# Sheet1.net
KiCad netlist of a schematic drawn in Altium Designer
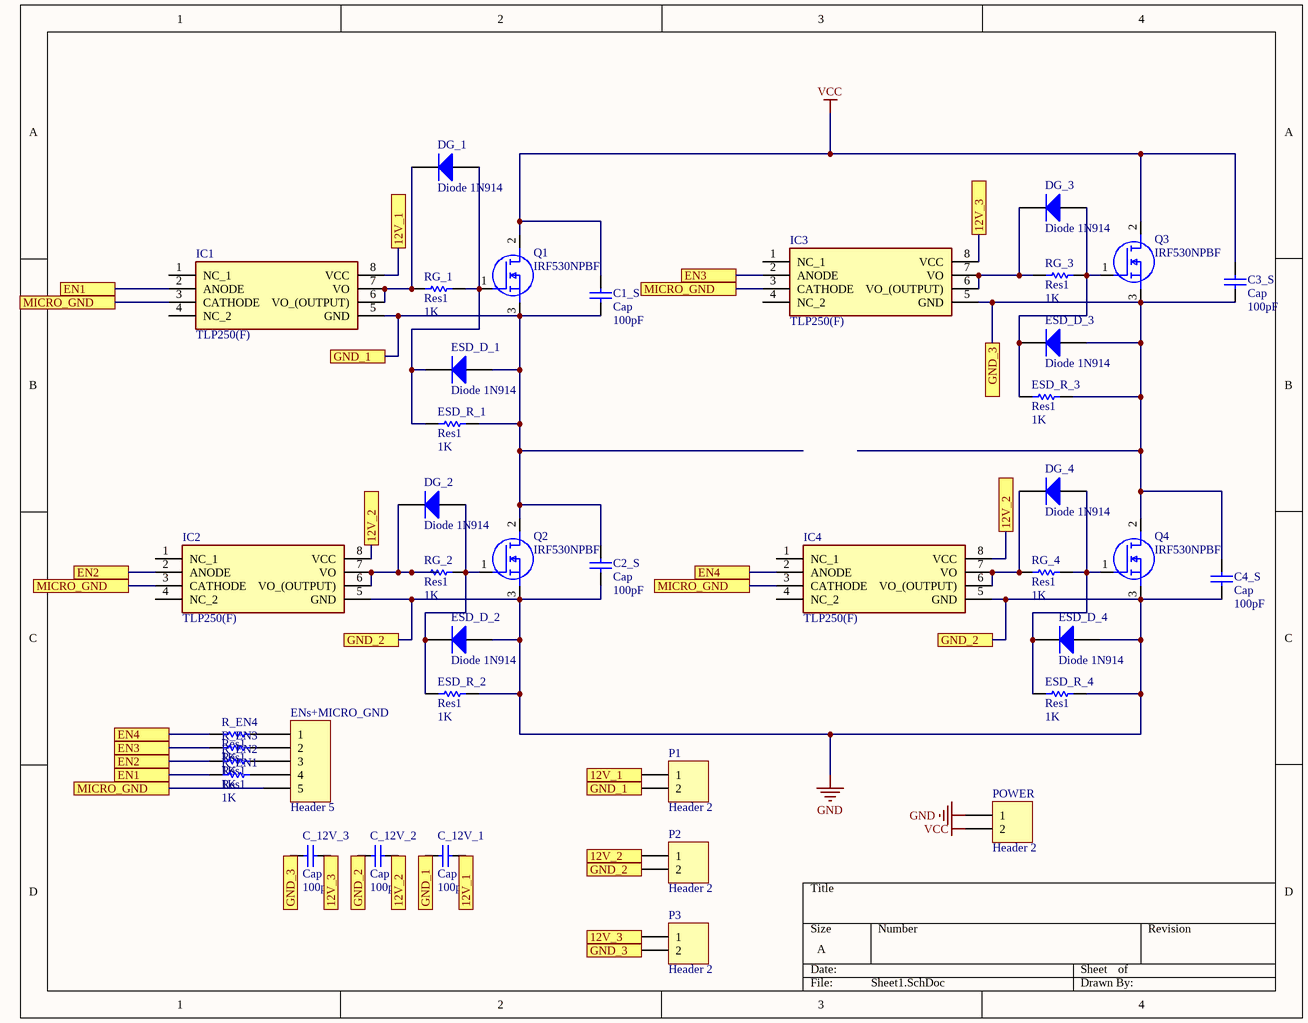
[diagram p0: Sheet1.SchDoc]

(export (version "E")
  (design (tool "Eeschema 10.0.6"))
  (components
    (comp (ref "C1_S")
      (value "Cap")
      (footprint "RAD-0.3")
      (description "Capacitor")
      (fields (field (name "ALTIUM_VALUE") "100pF") (field (name "PUBLISHER") "Altium Limited"))
      (libsource (lib "Miscellaneous Devices") (part "Cap"))
    )
    (comp (ref "C2_S")
      (value "Cap")
      (footprint "RAD-0.3")
      (description "Capacitor")
      (fields (field (name "ALTIUM_VALUE") "100pF") (field (name "PUBLISHER") "Altium Limited"))
      (libsource (lib "Miscellaneous Devices") (part "Cap"))
    )
    (comp (ref "C3_S")
      (value "Cap")
      (footprint "RAD-0.3")
      (description "Capacitor")
      (fields (field (name "ALTIUM_VALUE") "100pF") (field (name "PUBLISHER") "Altium Limited"))
      (libsource (lib "Miscellaneous Devices") (part "Cap"))
    )
    (comp (ref "C4_S")
      (value "Cap")
      (footprint "RAD-0.3")
      (description "Capacitor")
      (fields (field (name "ALTIUM_VALUE") "100pF") (field (name "PUBLISHER") "Altium Limited"))
      (libsource (lib "Miscellaneous Devices") (part "Cap"))
    )
    (comp (ref "C_12V_1")
      (value "Cap")
      (footprint "RAD-0.3")
      (description "Capacitor")
      (fields (field (name "ALTIUM_VALUE") "100pF") (field (name "PUBLISHER") "Altium Limited"))
      (libsource (lib "Miscellaneous Devices") (part "Cap"))
    )
    (comp (ref "C_12V_2")
      (value "Cap")
      (footprint "RAD-0.3")
      (description "Capacitor")
      (fields (field (name "ALTIUM_VALUE") "100pF") (field (name "PUBLISHER") "Altium Limited"))
      (libsource (lib "Miscellaneous Devices") (part "Cap"))
    )
    (comp (ref "C_12V_3")
      (value "Cap")
      (footprint "RAD-0.3")
      (description "Capacitor")
      (fields (field (name "ALTIUM_VALUE") "100pF") (field (name "PUBLISHER") "Altium Limited"))
      (libsource (lib "Miscellaneous Devices") (part "Cap"))
    )
    (comp (ref "DG_1")
      (value "Diode 1N914")
      (footprint "DO-35")
      (description "High Conductance Fast Diode")
      (fields (field (name "PUBLISHER") "Altium Limited"))
      (libsource (lib "Miscellaneous Devices") (part "Diode 1N914"))
    )
    (comp (ref "DG_2")
      (value "Diode 1N914")
      (footprint "DO-35")
      (description "High Conductance Fast Diode")
      (fields (field (name "PUBLISHER") "Altium Limited"))
      (libsource (lib "Miscellaneous Devices") (part "Diode 1N914"))
    )
    (comp (ref "DG_3")
      (value "Diode 1N914")
      (footprint "DO-35")
      (description "High Conductance Fast Diode")
      (fields (field (name "PUBLISHER") "Altium Limited"))
      (libsource (lib "Miscellaneous Devices") (part "Diode 1N914"))
    )
    (comp (ref "DG_4")
      (value "Diode 1N914")
      (footprint "DO-35")
      (description "High Conductance Fast Diode")
      (fields (field (name "PUBLISHER") "Altium Limited"))
      (libsource (lib "Miscellaneous Devices") (part "Diode 1N914"))
    )
    (comp (ref "ENs+MICRO_GND")
      (value "Header 5")
      (footprint "HDR1X5")
      (description "Header, 5-Pin")
      (fields (field (name "PUBLISHER") "Altium Limited"))
      (libsource (lib "Miscellaneous Connectors") (part "Header 5"))
    )
    (comp (ref "ESD_D_1")
      (value "Diode 1N914")
      (footprint "DO-35")
      (description "High Conductance Fast Diode")
      (fields (field (name "PUBLISHER") "Altium Limited"))
      (libsource (lib "Miscellaneous Devices") (part "Diode 1N914"))
    )
    (comp (ref "ESD_D_2")
      (value "Diode 1N914")
      (footprint "DO-35")
      (description "High Conductance Fast Diode")
      (fields (field (name "PUBLISHER") "Altium Limited"))
      (libsource (lib "Miscellaneous Devices") (part "Diode 1N914"))
    )
    (comp (ref "ESD_D_3")
      (value "Diode 1N914")
      (footprint "DO-35")
      (description "High Conductance Fast Diode")
      (fields (field (name "PUBLISHER") "Altium Limited"))
      (libsource (lib "Miscellaneous Devices") (part "Diode 1N914"))
    )
    (comp (ref "ESD_D_4")
      (value "Diode 1N914")
      (footprint "DO-35")
      (description "High Conductance Fast Diode")
      (fields (field (name "PUBLISHER") "Altium Limited"))
      (libsource (lib "Miscellaneous Devices") (part "Diode 1N914"))
    )
    (comp (ref "ESD_R_1")
      (value "Res1")
      (footprint "AXIAL-0.3")
      (description "Resistor")
      (fields (field (name "ALTIUM_VALUE") "1K") (field (name "PUBLISHER") "Altium Limited"))
      (libsource (lib "Miscellaneous Devices") (part "Res1"))
    )
    (comp (ref "ESD_R_2")
      (value "Res1")
      (footprint "AXIAL-0.3")
      (description "Resistor")
      (fields (field (name "ALTIUM_VALUE") "1K") (field (name "PUBLISHER") "Altium Limited"))
      (libsource (lib "Miscellaneous Devices") (part "Res1"))
    )
    (comp (ref "ESD_R_3")
      (value "Res1")
      (footprint "AXIAL-0.3")
      (description "Resistor")
      (fields (field (name "ALTIUM_VALUE") "1K") (field (name "PUBLISHER") "Altium Limited"))
      (libsource (lib "Miscellaneous Devices") (part "Res1"))
    )
    (comp (ref "ESD_R_4")
      (value "Res1")
      (footprint "AXIAL-0.3")
      (description "Resistor")
      (fields (field (name "ALTIUM_VALUE") "1K") (field (name "PUBLISHER") "Altium Limited"))
      (libsource (lib "Miscellaneous Devices") (part "Res1"))
    )
    (comp (ref "IC1")
      (value "TLP250(F)")
      (footprint "SamacSys:DIP762W60P254L966H485Q8N")
      (description "Integrated Circuit")
      (fields (field (name "MOUSER PART NUMBER") "757-TLP250(F)") (field (name "RS PART NUMBER") "1000151P"))
      (libsource (lib "*") (part "TLP250(F)"))
    )
    (comp (ref "IC2")
      (value "TLP250(F)")
      (footprint "SamacSys:DIP762W60P254L966H485Q8N")
      (description "Integrated Circuit")
      (fields (field (name "MOUSER PART NUMBER") "757-TLP250(F)") (field (name "RS PART NUMBER") "1000151P"))
      (libsource (lib "*") (part "TLP250(F)"))
    )
    (comp (ref "IC3")
      (value "TLP250(F)")
      (footprint "SamacSys:DIP762W60P254L966H485Q8N")
      (description "Integrated Circuit")
      (fields (field (name "MOUSER PART NUMBER") "757-TLP250(F)") (field (name "RS PART NUMBER") "1000151P"))
      (libsource (lib "*") (part "TLP250(F)"))
    )
    (comp (ref "IC4")
      (value "TLP250(F)")
      (footprint "SamacSys:DIP762W60P254L966H485Q8N")
      (description "Integrated Circuit")
      (fields (field (name "MOUSER PART NUMBER") "757-TLP250(F)") (field (name "RS PART NUMBER") "1000151P"))
      (libsource (lib "*") (part "TLP250(F)"))
    )
    (comp (ref "P1")
      (value "Header 2")
      (footprint "HDR1X2")
      (description "Header, 2-Pin")
      (fields (field (name "PUBLISHER") "Altium Limited"))
      (libsource (lib "Miscellaneous Connectors") (part "Header 2"))
    )
    (comp (ref "P2")
      (value "Header 2")
      (footprint "HDR1X2")
      (description "Header, 2-Pin")
      (fields (field (name "PUBLISHER") "Altium Limited"))
      (libsource (lib "Miscellaneous Connectors") (part "Header 2"))
    )
    (comp (ref "P3")
      (value "Header 2")
      (footprint "HDR1X2")
      (description "Header, 2-Pin")
      (fields (field (name "PUBLISHER") "Altium Limited"))
      (libsource (lib "Miscellaneous Connectors") (part "Header 2"))
    )
    (comp (ref "POWER")
      (value "Header 2")
      (footprint "HDR1X2")
      (description "Header, 2-Pin")
      (fields (field (name "PUBLISHER") "Altium Limited"))
      (libsource (lib "Miscellaneous Connectors") (part "Header 2"))
    )
    (comp (ref "Q1")
      (value "IRF530NPBF")
      (footprint "SamacSys:TO254P469X1042X1967-3P")
      (description "MOSFET (N-Channel)")
      (fields (field (name "MOUSER PART NUMBER") "942-IRF530NPBF") (field (name "RS PART NUMBER") "5410755P"))
      (libsource (lib "*") (part "IRF530NPBF"))
    )
    (comp (ref "Q2")
      (value "IRF530NPBF")
      (footprint "SamacSys:TO254P469X1042X1967-3P")
      (description "MOSFET (N-Channel)")
      (fields (field (name "MOUSER PART NUMBER") "942-IRF530NPBF") (field (name "RS PART NUMBER") "5410755P"))
      (libsource (lib "*") (part "IRF530NPBF"))
    )
    (comp (ref "Q3")
      (value "IRF530NPBF")
      (footprint "SamacSys:TO254P469X1042X1967-3P")
      (description "MOSFET (N-Channel)")
      (fields (field (name "MOUSER PART NUMBER") "942-IRF530NPBF") (field (name "RS PART NUMBER") "5410755P"))
      (libsource (lib "*") (part "IRF530NPBF"))
    )
    (comp (ref "Q4")
      (value "IRF530NPBF")
      (footprint "SamacSys:TO254P469X1042X1967-3P")
      (description "MOSFET (N-Channel)")
      (fields (field (name "MOUSER PART NUMBER") "942-IRF530NPBF") (field (name "RS PART NUMBER") "5410755P"))
      (libsource (lib "*") (part "IRF530NPBF"))
    )
    (comp (ref "RG_1")
      (value "Res1")
      (footprint "AXIAL-0.3")
      (description "Resistor")
      (fields (field (name "ALTIUM_VALUE") "1K") (field (name "PUBLISHER") "Altium Limited"))
      (libsource (lib "Miscellaneous Devices") (part "Res1"))
    )
    (comp (ref "RG_2")
      (value "Res1")
      (footprint "AXIAL-0.3")
      (description "Resistor")
      (fields (field (name "ALTIUM_VALUE") "1K") (field (name "PUBLISHER") "Altium Limited"))
      (libsource (lib "Miscellaneous Devices") (part "Res1"))
    )
    (comp (ref "RG_3")
      (value "Res1")
      (footprint "AXIAL-0.3")
      (description "Resistor")
      (fields (field (name "ALTIUM_VALUE") "1K") (field (name "PUBLISHER") "Altium Limited"))
      (libsource (lib "Miscellaneous Devices") (part "Res1"))
    )
    (comp (ref "RG_4")
      (value "Res1")
      (footprint "AXIAL-0.3")
      (description "Resistor")
      (fields (field (name "ALTIUM_VALUE") "1K") (field (name "PUBLISHER") "Altium Limited"))
      (libsource (lib "Miscellaneous Devices") (part "Res1"))
    )
    (comp (ref "R_EN1")
      (value "Res1")
      (footprint "AXIAL-0.3")
      (description "Resistor")
      (fields (field (name "ALTIUM_VALUE") "1K") (field (name "PUBLISHER") "Altium Limited"))
      (libsource (lib "Miscellaneous Devices") (part "Res1"))
    )
    (comp (ref "R_EN2")
      (value "Res1")
      (footprint "AXIAL-0.3")
      (description "Resistor")
      (fields (field (name "ALTIUM_VALUE") "1K") (field (name "PUBLISHER") "Altium Limited"))
      (libsource (lib "Miscellaneous Devices") (part "Res1"))
    )
    (comp (ref "R_EN3")
      (value "Res1")
      (footprint "AXIAL-0.3")
      (description "Resistor")
      (fields (field (name "ALTIUM_VALUE") "1K") (field (name "PUBLISHER") "Altium Limited"))
      (libsource (lib "Miscellaneous Devices") (part "Res1"))
    )
    (comp (ref "R_EN4")
      (value "Res1")
      (footprint "AXIAL-0.3")
      (description "Resistor")
      (fields (field (name "ALTIUM_VALUE") "1K") (field (name "PUBLISHER") "Altium Limited"))
      (libsource (lib "Miscellaneous Devices") (part "Res1"))
    )
  )
  (nets
    (net (code "1") (name "/12V_1") (class "Default")
      (node (ref "C_12V_1") (pin "2") (pinfunction "2_2") (pintype "passive"))
      (node (ref "IC1") (pin "8") (pinfunction "VCC_8") (pintype "passive"))
      (node (ref "P1") (pin "1") (pinfunction "1_1") (pintype "passive"))
    )
    (net (code "2") (name "/12V_2") (class "Default")
      (node (ref "C_12V_2") (pin "2") (pinfunction "2_2") (pintype "passive"))
      (node (ref "IC2") (pin "8") (pinfunction "VCC_8") (pintype "passive"))
      (node (ref "IC4") (pin "8") (pinfunction "VCC_8") (pintype "passive"))
      (node (ref "P2") (pin "1") (pinfunction "1_1") (pintype "passive"))
    )
    (net (code "3") (name "/12V_3") (class "Default")
      (node (ref "C_12V_3") (pin "2") (pinfunction "2_2") (pintype "passive"))
      (node (ref "IC3") (pin "8") (pinfunction "VCC_8") (pintype "passive"))
      (node (ref "P3") (pin "1") (pinfunction "1_1") (pintype "passive"))
    )
    (net (code "4") (name "/EN1") (class "Default")
      (node (ref "IC1") (pin "2") (pinfunction "ANODE_2") (pintype "passive"))
      (node (ref "R_EN1") (pin "1") (pinfunction "1_1") (pintype "passive"))
    )
    (net (code "5") (name "/EN2") (class "Default")
      (node (ref "IC2") (pin "2") (pinfunction "ANODE_2") (pintype "passive"))
      (node (ref "R_EN2") (pin "1") (pinfunction "1_1") (pintype "passive"))
    )
    (net (code "6") (name "/EN3") (class "Default")
      (node (ref "IC3") (pin "2") (pinfunction "ANODE_2") (pintype "passive"))
      (node (ref "R_EN3") (pin "1") (pinfunction "1_1") (pintype "passive"))
    )
    (net (code "7") (name "/EN4") (class "Default")
      (node (ref "IC4") (pin "2") (pinfunction "ANODE_2") (pintype "passive"))
      (node (ref "R_EN4") (pin "1") (pinfunction "1_1") (pintype "passive"))
    )
    (net (code "8") (name "/GND_1") (class "Default")
      (node (ref "C1_S") (pin "1") (pinfunction "1_1") (pintype "passive"))
      (node (ref "C2_S") (pin "2") (pinfunction "2_2") (pintype "passive"))
      (node (ref "C_12V_1") (pin "1") (pinfunction "1_1") (pintype "passive"))
      (node (ref "ESD_D_1") (pin "1") (pinfunction "A_1") (pintype "passive"))
      (node (ref "ESD_R_1") (pin "2") (pinfunction "2_2") (pintype "passive"))
      (node (ref "IC1") (pin "5") (pinfunction "GND_5") (pintype "passive"))
      (node (ref "P1") (pin "2") (pinfunction "2_2") (pintype "passive"))
      (node (ref "Q1") (pin "3") (pinfunction "S_3") (pintype "passive"))
      (node (ref "Q2") (pin "2") (pinfunction "D_2") (pintype "passive"))
    )
    (net (code "9") (name "/GND_3") (class "Default")
      (node (ref "C3_S") (pin "1") (pinfunction "1_1") (pintype "passive"))
      (node (ref "C4_S") (pin "2") (pinfunction "2_2") (pintype "passive"))
      (node (ref "C_12V_3") (pin "1") (pinfunction "1_1") (pintype "passive"))
      (node (ref "ESD_D_3") (pin "1") (pinfunction "A_1") (pintype "passive"))
      (node (ref "ESD_R_3") (pin "2") (pinfunction "2_2") (pintype "passive"))
      (node (ref "IC3") (pin "5") (pinfunction "GND_5") (pintype "passive"))
      (node (ref "P3") (pin "2") (pinfunction "2_2") (pintype "passive"))
      (node (ref "Q3") (pin "3") (pinfunction "S_3") (pintype "passive"))
      (node (ref "Q4") (pin "2") (pinfunction "D_2") (pintype "passive"))
    )
    (net (code "10") (name "/MICRO_GND") (class "Default")
      (node (ref "ENs+MICRO_GND") (pin "5") (pinfunction "5_5") (pintype "passive"))
      (node (ref "IC1") (pin "3") (pinfunction "CATHODE_3") (pintype "passive"))
      (node (ref "IC2") (pin "3") (pinfunction "CATHODE_3") (pintype "passive"))
      (node (ref "IC3") (pin "3") (pinfunction "CATHODE_3") (pintype "passive"))
      (node (ref "IC4") (pin "3") (pinfunction "CATHODE_3") (pintype "passive"))
    )
    (net (code "11") (name "GND") (class "Default")
      (node (ref "C2_S") (pin "1") (pinfunction "1_1") (pintype "passive"))
      (node (ref "C4_S") (pin "1") (pinfunction "1_1") (pintype "passive"))
      (node (ref "C_12V_2") (pin "1") (pinfunction "1_1") (pintype "passive"))
      (node (ref "ESD_D_2") (pin "1") (pinfunction "A_1") (pintype "passive"))
      (node (ref "ESD_D_4") (pin "1") (pinfunction "A_1") (pintype "passive"))
      (node (ref "ESD_R_2") (pin "2") (pinfunction "2_2") (pintype "passive"))
      (node (ref "ESD_R_4") (pin "2") (pinfunction "2_2") (pintype "passive"))
      (node (ref "IC2") (pin "5") (pinfunction "GND_5") (pintype "passive"))
      (node (ref "IC4") (pin "5") (pinfunction "GND_5") (pintype "passive"))
      (node (ref "P2") (pin "2") (pinfunction "2_2") (pintype "passive"))
      (node (ref "POWER") (pin "1") (pinfunction "1_1") (pintype "passive"))
      (node (ref "Q2") (pin "3") (pinfunction "S_3") (pintype "passive"))
      (node (ref "Q4") (pin "3") (pinfunction "S_3") (pintype "passive"))
    )
    (net (code "12") (name "Net-(DG_1-A)") (class "Default")
      (node (ref "DG_1") (pin "1") (pinfunction "A_1") (pintype "passive"))
      (node (ref "ESD_D_1") (pin "2") (pinfunction "K_2") (pintype "passive"))
      (node (ref "ESD_R_1") (pin "1") (pinfunction "1_1") (pintype "passive"))
      (node (ref "Q1") (pin "1") (pinfunction "G_1") (pintype "passive"))
      (node (ref "RG_1") (pin "2") (pinfunction "2_2") (pintype "passive"))
    )
    (net (code "13") (name "Net-(DG_1-K)") (class "Default")
      (node (ref "DG_1") (pin "2") (pinfunction "K_2") (pintype "passive"))
      (node (ref "IC1") (pin "6") (pinfunction "VO_(OUTPUT)_6") (pintype "passive"))
      (node (ref "IC1") (pin "7") (pinfunction "VO_7") (pintype "passive"))
      (node (ref "RG_1") (pin "1") (pinfunction "1_1") (pintype "passive"))
    )
    (net (code "14") (name "Net-(DG_2-A)") (class "Default")
      (node (ref "DG_2") (pin "1") (pinfunction "A_1") (pintype "passive"))
      (node (ref "ESD_D_2") (pin "2") (pinfunction "K_2") (pintype "passive"))
      (node (ref "ESD_R_2") (pin "1") (pinfunction "1_1") (pintype "passive"))
      (node (ref "Q2") (pin "1") (pinfunction "G_1") (pintype "passive"))
      (node (ref "RG_2") (pin "2") (pinfunction "2_2") (pintype "passive"))
    )
    (net (code "15") (name "Net-(DG_2-K)") (class "Default")
      (node (ref "DG_2") (pin "2") (pinfunction "K_2") (pintype "passive"))
      (node (ref "IC2") (pin "6") (pinfunction "VO_(OUTPUT)_6") (pintype "passive"))
      (node (ref "IC2") (pin "7") (pinfunction "VO_7") (pintype "passive"))
      (node (ref "RG_2") (pin "1") (pinfunction "1_1") (pintype "passive"))
    )
    (net (code "16") (name "Net-(DG_3-A)") (class "Default")
      (node (ref "DG_3") (pin "1") (pinfunction "A_1") (pintype "passive"))
      (node (ref "ESD_D_3") (pin "2") (pinfunction "K_2") (pintype "passive"))
      (node (ref "ESD_R_3") (pin "1") (pinfunction "1_1") (pintype "passive"))
      (node (ref "Q3") (pin "1") (pinfunction "G_1") (pintype "passive"))
      (node (ref "RG_3") (pin "2") (pinfunction "2_2") (pintype "passive"))
    )
    (net (code "17") (name "Net-(DG_3-K)") (class "Default")
      (node (ref "DG_3") (pin "2") (pinfunction "K_2") (pintype "passive"))
      (node (ref "IC3") (pin "6") (pinfunction "VO_(OUTPUT)_6") (pintype "passive"))
      (node (ref "IC3") (pin "7") (pinfunction "VO_7") (pintype "passive"))
      (node (ref "RG_3") (pin "1") (pinfunction "1_1") (pintype "passive"))
    )
    (net (code "18") (name "Net-(DG_4-A)") (class "Default")
      (node (ref "DG_4") (pin "1") (pinfunction "A_1") (pintype "passive"))
      (node (ref "ESD_D_4") (pin "2") (pinfunction "K_2") (pintype "passive"))
      (node (ref "ESD_R_4") (pin "1") (pinfunction "1_1") (pintype "passive"))
      (node (ref "Q4") (pin "1") (pinfunction "G_1") (pintype "passive"))
      (node (ref "RG_4") (pin "2") (pinfunction "2_2") (pintype "passive"))
    )
    (net (code "19") (name "Net-(DG_4-K)") (class "Default")
      (node (ref "DG_4") (pin "2") (pinfunction "K_2") (pintype "passive"))
      (node (ref "IC4") (pin "6") (pinfunction "VO_(OUTPUT)_6") (pintype "passive"))
      (node (ref "IC4") (pin "7") (pinfunction "VO_7") (pintype "passive"))
      (node (ref "RG_4") (pin "1") (pinfunction "1_1") (pintype "passive"))
    )
    (net (code "20") (name "Net-(ENs+MICRO_GND-Pad1)") (class "Default")
      (node (ref "ENs+MICRO_GND") (pin "1") (pinfunction "1_1") (pintype "passive"))
      (node (ref "R_EN4") (pin "2") (pinfunction "2_2") (pintype "passive"))
    )
    (net (code "21") (name "Net-(ENs+MICRO_GND-Pad2)") (class "Default")
      (node (ref "ENs+MICRO_GND") (pin "2") (pinfunction "2_2") (pintype "passive"))
      (node (ref "R_EN3") (pin "2") (pinfunction "2_2") (pintype "passive"))
    )
    (net (code "22") (name "Net-(ENs+MICRO_GND-Pad3)") (class "Default")
      (node (ref "ENs+MICRO_GND") (pin "3") (pinfunction "3_3") (pintype "passive"))
      (node (ref "R_EN2") (pin "2") (pinfunction "2_2") (pintype "passive"))
    )
    (net (code "23") (name "Net-(ENs+MICRO_GND-Pad4)") (class "Default")
      (node (ref "ENs+MICRO_GND") (pin "4") (pinfunction "4_4") (pintype "passive"))
      (node (ref "R_EN1") (pin "2") (pinfunction "2_2") (pintype "passive"))
    )
    (net (code "24") (name "VCC") (class "Default")
      (node (ref "C1_S") (pin "2") (pinfunction "2_2") (pintype "passive"))
      (node (ref "C3_S") (pin "2") (pinfunction "2_2") (pintype "passive"))
      (node (ref "POWER") (pin "2") (pinfunction "2_2") (pintype "passive"))
      (node (ref "Q1") (pin "2") (pinfunction "D_2") (pintype "passive"))
      (node (ref "Q3") (pin "2") (pinfunction "D_2") (pintype "passive"))
    )
    (net (code "25") (name "unconnected-(IC1-NC_1-Pad1)") (class "Default")
      (node (ref "IC1") (pin "1") (pinfunction "NC_1_1") (pintype "passive"))
    )
    (net (code "26") (name "unconnected-(IC1-NC_2-Pad4)") (class "Default")
      (node (ref "IC1") (pin "4") (pinfunction "NC_2_4") (pintype "passive"))
    )
    (net (code "27") (name "unconnected-(IC2-NC_1-Pad1)") (class "Default")
      (node (ref "IC2") (pin "1") (pinfunction "NC_1_1") (pintype "passive"))
    )
    (net (code "28") (name "unconnected-(IC2-NC_2-Pad4)") (class "Default")
      (node (ref "IC2") (pin "4") (pinfunction "NC_2_4") (pintype "passive"))
    )
    (net (code "29") (name "unconnected-(IC3-NC_1-Pad1)") (class "Default")
      (node (ref "IC3") (pin "1") (pinfunction "NC_1_1") (pintype "passive"))
    )
    (net (code "30") (name "unconnected-(IC3-NC_2-Pad4)") (class "Default")
      (node (ref "IC3") (pin "4") (pinfunction "NC_2_4") (pintype "passive"))
    )
    (net (code "31") (name "unconnected-(IC4-NC_1-Pad1)") (class "Default")
      (node (ref "IC4") (pin "1") (pinfunction "NC_1_1") (pintype "passive"))
    )
    (net (code "32") (name "unconnected-(IC4-NC_2-Pad4)") (class "Default")
      (node (ref "IC4") (pin "4") (pinfunction "NC_2_4") (pintype "passive"))
    )
  )
)
